# AET_mcu.net
KiCad netlist of a schematic drawn in Altium Designer
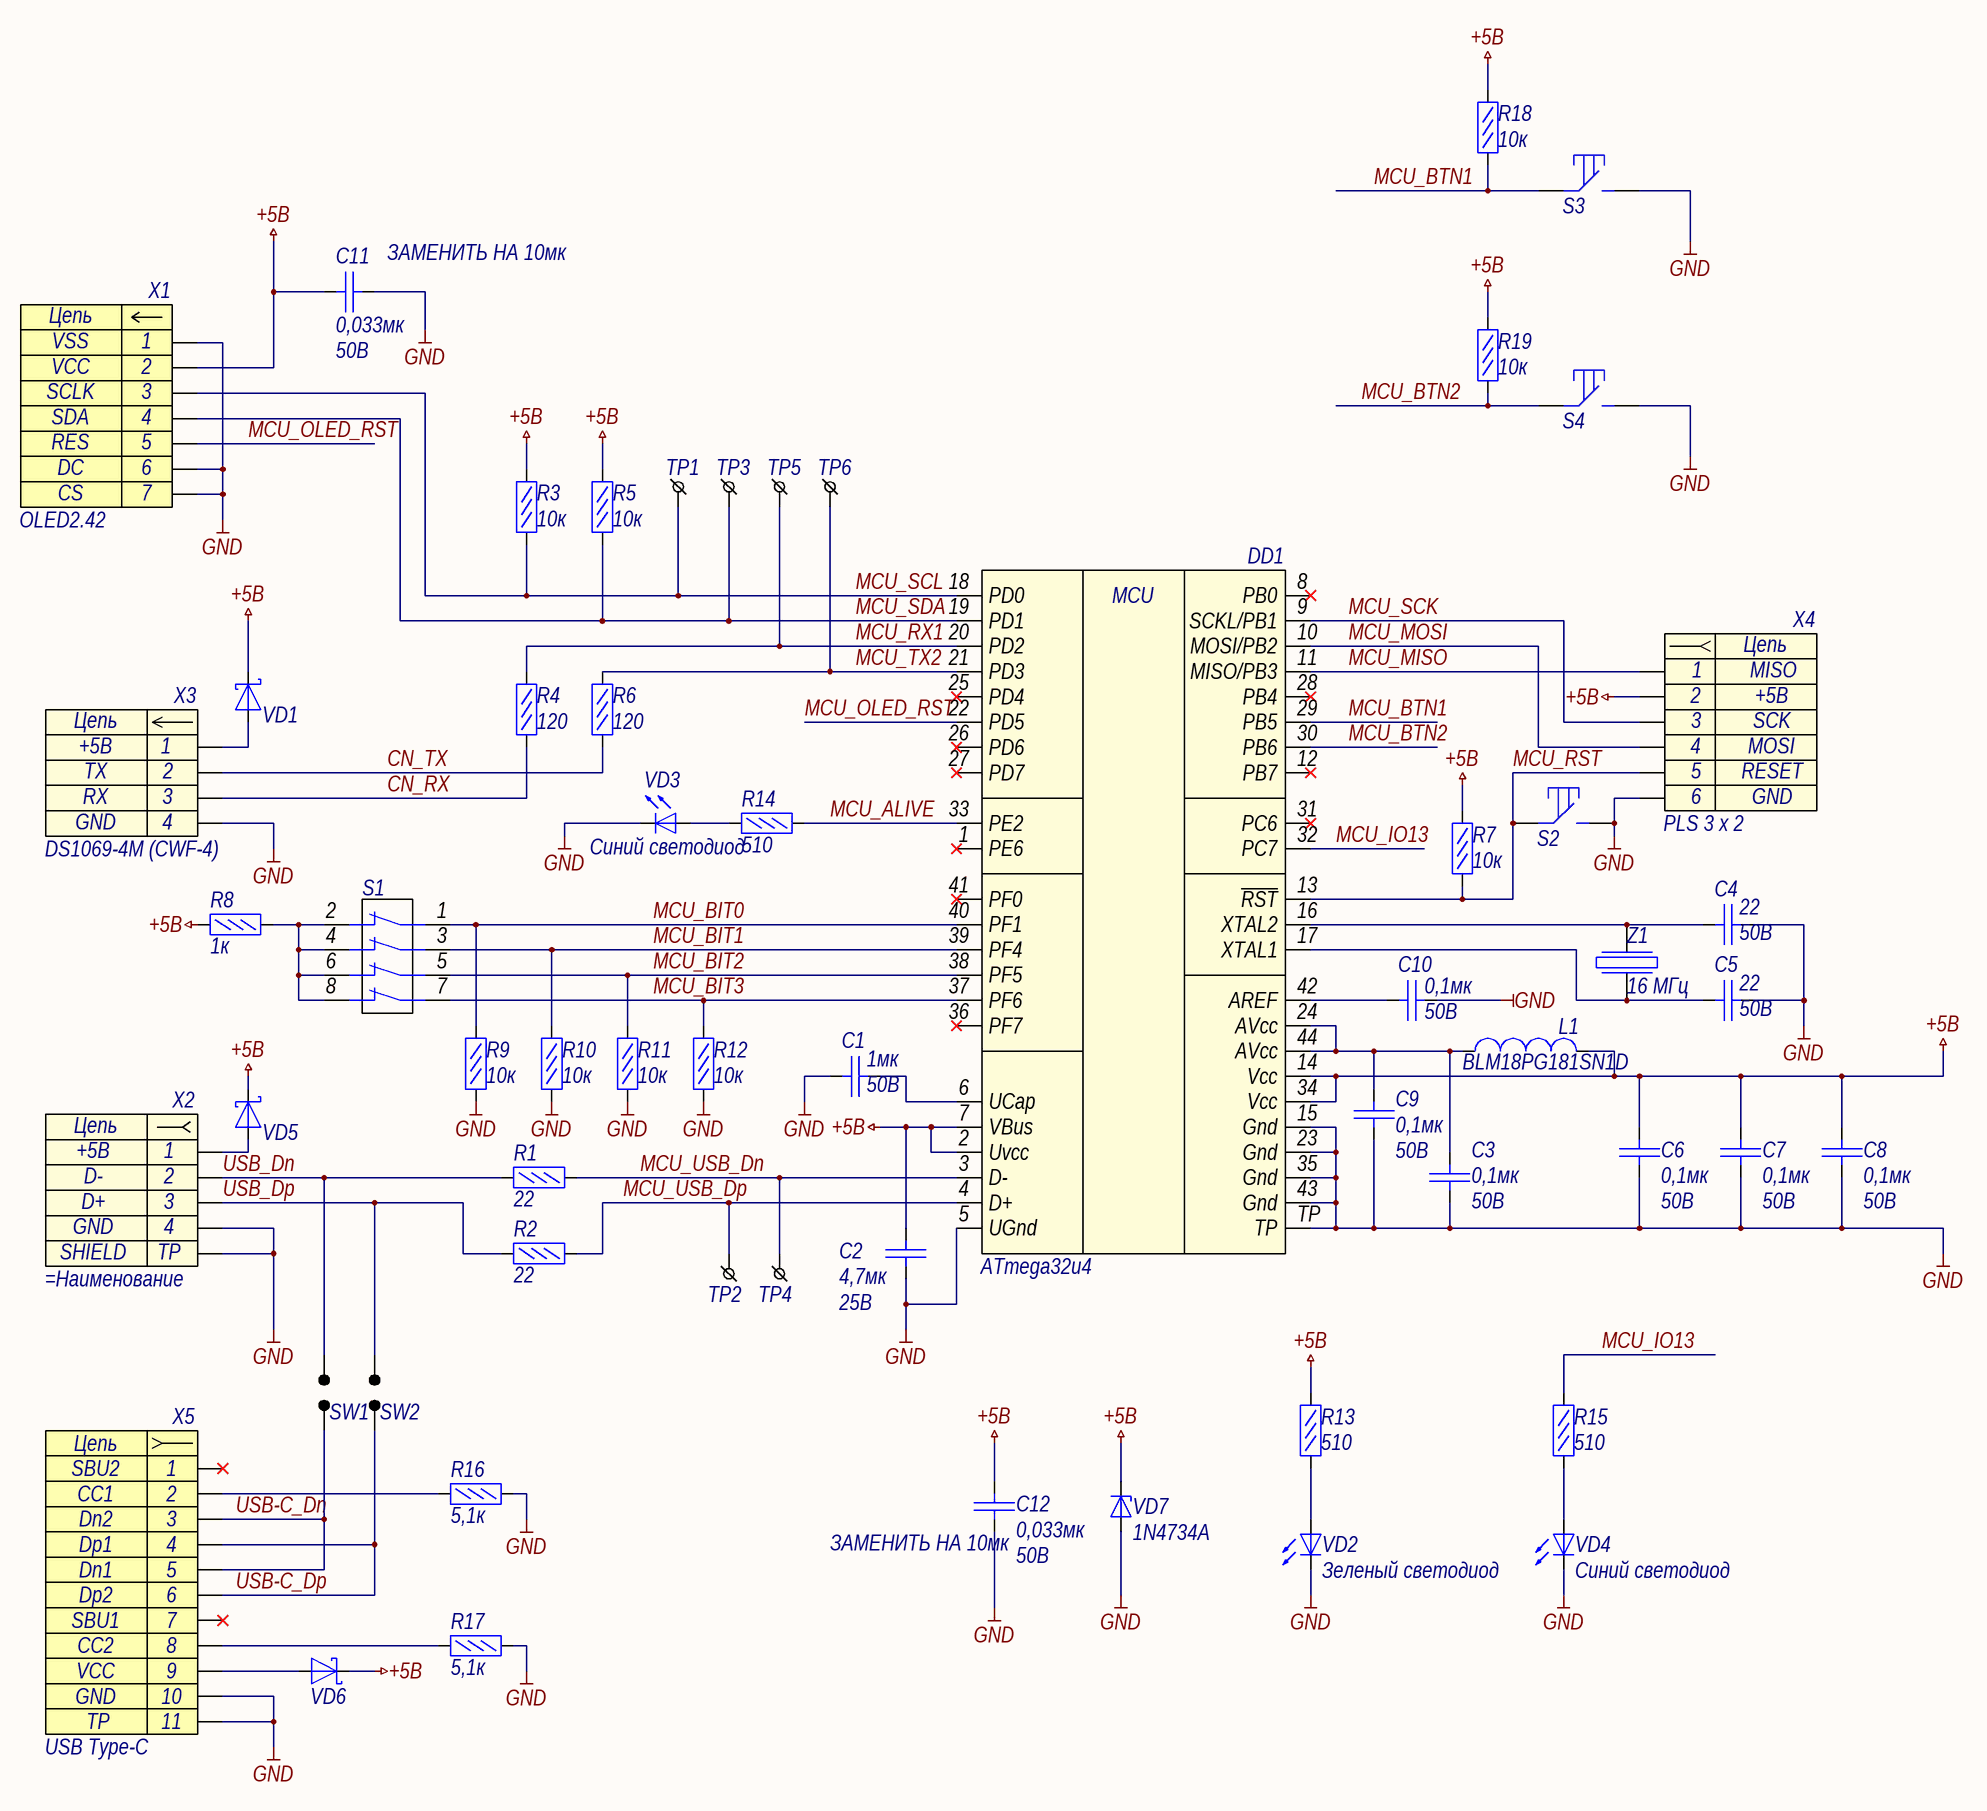
[diagram p0: AET_mcu.SchDoc]

(export (version "E")
  (design (tool "Eeschema 10.0.6"))
  (components
    (comp (ref "C1")
      (value "1мк")
      (footprint "C0603")
      (description "Конденсатор кер. 1мкФ 50В")
      (fields (field (name "MANUFACTURER") "Yageo") (field (name "VOLTAGE") "50В"))
      (libsource (lib "capacitors") (part "CC0603KRX7R9BB105"))
    )
    (comp (ref "C2")
      (value "4,7мк")
      (footprint "C0603")
      (description "Конденсатор кер. 4,7мкФ 25В")
      (fields (field (name "MANUFACTURER") "Yageo") (field (name "VOLTAGE") "25В"))
      (libsource (lib "capacitors") (part "CC0603KRX5R8BB475"))
    )
    (comp (ref "C3")
      (value "0,1мк")
      (footprint "C0603")
      (description "Конденсатор кер. 0,1мкФ 50В")
      (fields (field (name "MANUFACTURER") "Yageo") (field (name "VOLTAGE") "50В"))
      (libsource (lib "capacitors") (part "CC0603JPX7R9BB104"))
    )
    (comp (ref "C4")
      (value "22")
      (footprint "C0603")
      (description "Конденсатор кер. 22пФ 50В")
      (fields (field (name "MANUFACTURER") "Yageo") (field (name "VOLTAGE") "50В"))
      (libsource (lib "capacitors") (part "CC0603JRNPO9BN220"))
    )
    (comp (ref "C5")
      (value "22")
      (footprint "C0603")
      (description "Конденсатор кер. 22пФ 50В")
      (fields (field (name "MANUFACTURER") "Yageo") (field (name "VOLTAGE") "50В"))
      (libsource (lib "capacitors") (part "CC0603JRNPO9BN220"))
    )
    (comp (ref "C6")
      (value "0,1мк")
      (footprint "C0603")
      (description "Конденсатор кер. 0,1мкФ 50В")
      (fields (field (name "MANUFACTURER") "Yageo") (field (name "VOLTAGE") "50В"))
      (libsource (lib "capacitors") (part "CC0603JPX7R9BB104"))
    )
    (comp (ref "C7")
      (value "0,1мк")
      (footprint "C0603")
      (description "Конденсатор кер. 0,1мкФ 50В")
      (fields (field (name "MANUFACTURER") "Yageo") (field (name "VOLTAGE") "50В"))
      (libsource (lib "capacitors") (part "CC0603JPX7R9BB104"))
    )
    (comp (ref "C8")
      (value "0,1мк")
      (footprint "C0603")
      (description "Конденсатор кер. 0,1мкФ 50В")
      (fields (field (name "MANUFACTURER") "Yageo") (field (name "VOLTAGE") "50В"))
      (libsource (lib "capacitors") (part "CC0603JPX7R9BB104"))
    )
    (comp (ref "C9")
      (value "0,1мк")
      (footprint "C0603")
      (description "Конденсатор кер. 0,1мкФ 50В")
      (fields (field (name "MANUFACTURER") "Yageo") (field (name "VOLTAGE") "50В"))
      (libsource (lib "capacitors") (part "CC0603JPX7R9BB104"))
    )
    (comp (ref "C10")
      (value "0,1мк")
      (footprint "C0603")
      (description "Конденсатор кер. 0,1мкФ 50В")
      (fields (field (name "MANUFACTURER") "Yageo") (field (name "VOLTAGE") "50В"))
      (libsource (lib "capacitors") (part "CC0603JPX7R9BB104"))
    )
    (comp (ref "C11")
      (value "0,033мк")
      (footprint "C1206")
      (description "Конденсатор кер. 0,033мкФ 50В NP0")
      (fields (field (name "MANUFACTURER") "Murata") (field (name "VOLTAGE") "50В"))
      (libsource (lib "capacitors") (part "GRM3195C1H333J"))
    )
    (comp (ref "C12")
      (value "0,033мк")
      (footprint "C1206")
      (description "Конденсатор кер. 0,033мкФ 50В NP0")
      (fields (field (name "MANUFACTURER") "Murata") (field (name "VOLTAGE") "50В"))
      (libsource (lib "capacitors") (part "GRM3195C1H333J"))
    )
    (comp (ref "DD1")
      (value "ATmega32u4")
      (footprint "UNIVERSAL_ATMEGA32U4")
      (description "Микроконтроллер AVR 8-bit")
      (libsource (lib "MCU") (part "ATMEGA32U4"))
    )
    (comp (ref "L1")
      (value "BLM18PG181SN1D")
      (footprint "L0603")
      (description "Ферритовая бусина 180Ом 1,5А")
      (fields (field (name "MANUFACTURER") "Murata"))
      (libsource (lib "inductance") (part "BLM18PG181SN1D"))
    )
    (comp (ref "R1")
      (value "22")
      (footprint "R0603")
      (description "Резистор 22 Ом 0,1Вт 1%")
      (fields (field (name "MANUFACTURER") "YAGEO") (field (name "TOLERANCE") "1%"))
      (libsource (lib "resistors") (part "RC0603FR-0722RL"))
    )
    (comp (ref "R2")
      (value "22")
      (footprint "R0603")
      (description "Резистор 22 Ом 0,1Вт 1%")
      (fields (field (name "MANUFACTURER") "YAGEO") (field (name "TOLERANCE") "1%"))
      (libsource (lib "resistors") (part "RC0603FR-0722RL"))
    )
    (comp (ref "R3")
      (value "10к")
      (footprint "R0603")
      (description "Резистор 10кОм 0,063Вт 1%")
      (fields (field (name "MANUFACTURER") "YAGEO") (field (name "TOLERANCE") "1%"))
      (libsource (lib "resistors") (part "RC0603FR-0710KL"))
    )
    (comp (ref "R4")
      (value "120")
      (footprint "R0603")
      (description "Резистор 120Ом 0,063Вт 1%")
      (fields (field (name "MANUFACTURER") "YAGEO") (field (name "TOLERANCE") "1%"))
      (libsource (lib "resistors") (part "RC0603FR-07120RL"))
    )
    (comp (ref "R5")
      (value "10к")
      (footprint "R0603")
      (description "Резистор 10кОм 0,063Вт 1%")
      (fields (field (name "MANUFACTURER") "YAGEO") (field (name "TOLERANCE") "1%"))
      (libsource (lib "resistors") (part "RC0603FR-0710KL"))
    )
    (comp (ref "R6")
      (value "120")
      (footprint "R0603")
      (description "Резистор 120Ом 0,063Вт 1%")
      (fields (field (name "MANUFACTURER") "YAGEO") (field (name "TOLERANCE") "1%"))
      (libsource (lib "resistors") (part "RC0603FR-07120RL"))
    )
    (comp (ref "R7")
      (value "10к")
      (footprint "R0603")
      (description "Резистор 10кОм 0,063Вт 1%")
      (fields (field (name "MANUFACTURER") "YAGEO") (field (name "TOLERANCE") "1%"))
      (libsource (lib "resistors") (part "RC0603FR-0710KL"))
    )
    (comp (ref "R8")
      (value "1к")
      (footprint "R0603")
      (description "Резистор 1кОм 0,063Вт 1%")
      (fields (field (name "MANUFACTURER") "YAGEO") (field (name "TOLERANCE") "1%"))
      (libsource (lib "resistors") (part "RC0603FR-071KL"))
    )
    (comp (ref "R9")
      (value "10к")
      (footprint "R0603")
      (description "Резистор 10кОм 0,063Вт 1%")
      (fields (field (name "MANUFACTURER") "YAGEO") (field (name "TOLERANCE") "1%"))
      (libsource (lib "resistors") (part "RC0603FR-0710KL"))
    )
    (comp (ref "R10")
      (value "10к")
      (footprint "R0603")
      (description "Резистор 10кОм 0,063Вт 1%")
      (fields (field (name "MANUFACTURER") "YAGEO") (field (name "TOLERANCE") "1%"))
      (libsource (lib "resistors") (part "RC0603FR-0710KL"))
    )
    (comp (ref "R11")
      (value "10к")
      (footprint "R0603")
      (description "Резистор 10кОм 0,063Вт 1%")
      (fields (field (name "MANUFACTURER") "YAGEO") (field (name "TOLERANCE") "1%"))
      (libsource (lib "resistors") (part "RC0603FR-0710KL"))
    )
    (comp (ref "R12")
      (value "10к")
      (footprint "R0603")
      (description "Резистор 10кОм 0,063Вт 1%")
      (fields (field (name "MANUFACTURER") "YAGEO") (field (name "TOLERANCE") "1%"))
      (libsource (lib "resistors") (part "RC0603FR-0710KL"))
    )
    (comp (ref "R13")
      (value "510")
      (footprint "R0603")
      (description "Резистор 510 Ом 0,1Вт 1%")
      (fields (field (name "MANUFACTURER") "YAGEO") (field (name "TOLERANCE") "1%"))
      (libsource (lib "") (part "RC0603FR-07510RL_1"))
    )
    (comp (ref "R14")
      (value "510")
      (footprint "R0603")
      (description "Резистор 510 Ом 0,1Вт 1%")
      (fields (field (name "MANUFACTURER") "YAGEO") (field (name "TOLERANCE") "1%"))
      (libsource (lib "") (part "RC0603FR-07510RL_2"))
    )
    (comp (ref "R15")
      (value "510")
      (footprint "R0603")
      (description "Резистор 510 Ом 0,1Вт 1%")
      (fields (field (name "MANUFACTURER") "YAGEO") (field (name "TOLERANCE") "1%"))
      (libsource (lib "resistors") (part "RC0603FR-07510RL"))
    )
    (comp (ref "R16")
      (value "5,1к")
      (footprint "R0603")
      (description "Резистор 5,1кОм 0,1Вт 1%")
      (fields (field (name "MANUFACTURER") "YAGEO") (field (name "TOLERANCE") "1%"))
      (libsource (lib "resistors") (part "RC0603FR-075K1L"))
    )
    (comp (ref "R17")
      (value "5,1к")
      (footprint "R0603")
      (description "Резистор 5,1кОм 0,1Вт 1%")
      (fields (field (name "MANUFACTURER") "YAGEO") (field (name "TOLERANCE") "1%"))
      (libsource (lib "resistors") (part "RC0603FR-075K1L"))
    )
    (comp (ref "R18")
      (value "10к")
      (footprint "R0603")
      (description "Резистор 10кОм 0,063Вт 1%")
      (fields (field (name "MANUFACTURER") "YAGEO") (field (name "TOLERANCE") "1%"))
      (libsource (lib "") (part "RC0603FR-0710KL_1"))
    )
    (comp (ref "R19")
      (value "10к")
      (footprint "R0603")
      (description "Резистор 10кОм 0,063Вт 1%")
      (fields (field (name "MANUFACTURER") "YAGEO") (field (name "TOLERANCE") "1%"))
      (libsource (lib "") (part "RC0603FR-0710KL_1"))
    )
    (comp (ref "S1") (value "~") (footprint "A6S-4102-H") (libsource (lib "switches") (part "A6S-4102-H")))
    (comp (ref "S2")
      (value "IT-1187")
      (footprint "it-1187")
      (description "тактовая кнопка SMD")
      (libsource (lib "switches") (part "IT-1187"))
    )
    (comp (ref "S3")
      (value "IT-1198E")
      (footprint "IT-1198E")
      (description "боковая тактовая кнопка SMD")
      (libsource (lib "switches") (part "IT-1198E"))
    )
    (comp (ref "S4")
      (value "IT-1198E")
      (footprint "IT-1198E")
      (description "боковая тактовая кнопка SMD")
      (libsource (lib "switches") (part "IT-1198E"))
    )
    (comp (ref "SW1")
      (value "~")
      (footprint "JUMPER_SOLDERED_3x1")
      (description "Запаиваемая перемычка")
      (libsource (lib "mount_parts") (part "jumper"))
    )
    (comp (ref "SW2")
      (value "~")
      (footprint "JUMPER_SOLDERED_3x1")
      (description "Запаиваемая перемычка")
      (libsource (lib "mount_parts") (part "jumper"))
    )
    (comp (ref "TP1")
      (value "SCL")
      (footprint "TP_0,6X1")
      (libsource (lib "mount_parts") (part "TESTPOINT_HOLE"))
    )
    (comp (ref "TP2")
      (value "USB_Dp")
      (footprint "TP_0,6X1")
      (libsource (lib "mount_parts") (part "TESTPOINT_HOLE"))
    )
    (comp (ref "TP3")
      (value "SDA")
      (footprint "TP_0,6X1")
      (libsource (lib "mount_parts") (part "TESTPOINT_HOLE"))
    )
    (comp (ref "TP4")
      (value "USB_Dn")
      (footprint "TP_0,6X1")
      (libsource (lib "mount_parts") (part "TESTPOINT_HOLE"))
    )
    (comp (ref "TP5")
      (value "RX")
      (footprint "TP_0,6X1")
      (libsource (lib "mount_parts") (part "TESTPOINT_HOLE"))
    )
    (comp (ref "TP6")
      (value "TX")
      (footprint "TP_0,6X1")
      (libsource (lib "mount_parts") (part "TESTPOINT_HOLE"))
    )
    (comp (ref "VD1")
      (value "1N5817WS")
      (footprint "SOD323")
      (description "Диод Шоттки 1N5817WS 20V 1А 0.45V")
      (fields (field (name "VOLTAGE") "20В"))
      (libsource (lib "diodes") (part "1N5817WS"))
    )
    (comp (ref "VD2")
      (value "Зеленый светодиод")
      (footprint "VD0603")
      (description "Светодтод зеленый SMD Foryard Optoelectronics Co.")
      (libsource (lib "diodes") (part "FYLS-0603BUGC"))
    )
    (comp (ref "VD3")
      (value "Синий светодиод")
      (footprint "VD0603")
      (description "Светодтод синий SMD Foryard Optoelectronics Co.")
      (libsource (lib "diodes") (part "FYLS-0603BUBC"))
    )
    (comp (ref "VD4")
      (value "Синий светодиод")
      (footprint "VD0603")
      (description "Светодтод синий SMD Foryard Optoelectronics Co.")
      (libsource (lib "diodes") (part "FYLS-0603BUBC"))
    )
    (comp (ref "VD5")
      (value "1N5817WS")
      (footprint "SOD323")
      (description "Диод Шоттки 1N5817WS 20V 1А 0.45V")
      (fields (field (name "VOLTAGE") "20В"))
      (libsource (lib "diodes") (part "1N5817WS"))
    )
    (comp (ref "VD6")
      (value "1N5817WS")
      (footprint "SOD323")
      (description "Диод Шоттки 1N5817WS 20V 1А 0.45V")
      (fields (field (name "VOLTAGE") "20В"))
      (libsource (lib "diodes") (part "1N5817WS"))
    )
    (comp (ref "VD7")
      (value "1N4734A")
      (footprint "DO-41 Vertical")
      (description "Стабилитрон 5.6В, 5%, 1Вт, 1N4734A")
      (libsource (lib "diodes") (part "1N4734A"))
    )
    (comp (ref "X1")
      (value "OLED2.42")
      (footprint "OLED2.42-PLS2.54-1x7")
      (description "OLED дисплей 2.42inc - PLS2.54 - 1x7")
      (libsource (lib "headers") (part "OLED2,42 - header"))
    )
    (comp (ref "X2") (value "~") (footprint "USB-A") (libsource (lib "headers") (part "HEADER-USB-2.0")))
    (comp (ref "X3")
      (value "DS1069-4M (CWF-4)")
      (footprint "CWF-4")
      (description "Разъем - 4 конт. прямая вилка на плату")
      (fields (field (name "NAME") "DS1069-4M (CWF-4)"))
      (libsource (lib "headers") (part "CWF-4"))
    )
    (comp (ref "X4")
      (value "PLS 3 x 2")
      (footprint "pls-2,54-3x2-tht-v")
      (description "Разъем - 6 конт. 2x3, шаг 2,54 мм")
      (libsource (lib "headers") (part "PLS-3x2 ICSP"))
    )
    (comp (ref "X5")
      (value "USB Type-C")
      (footprint "USB4105-15-A-120")
      (description "USB Type-C USB4105-GF-A / GCT")
      (libsource (lib "headers") (part "USB4105-15-A-120"))
    )
    (comp (ref "Z1")
      (value "16 MГц")
      (footprint "QSMD3.2x2.5")
      (description "Кварцевый резонатор 16МГц")
      (fields (field (name "PARTNUMBER") "12.88605"))
      (libsource (lib "oscillators") (part "KX-7-16.0MHz"))
    )
  )
  (nets
    (net (code "1") (name "+5В") (class "Default")
      (node (ref "C11") (pin "2") (pinfunction "2_2") (pintype "passive"))
      (node (ref "C12") (pin "1") (pinfunction "1_1") (pintype "passive"))
      (node (ref "C2") (pin "2") (pinfunction "2_2") (pintype "passive"))
      (node (ref "C6") (pin "2") (pinfunction "2_2") (pintype "passive"))
      (node (ref "C7") (pin "2") (pinfunction "2_2") (pintype "passive"))
      (node (ref "C8") (pin "2") (pinfunction "2_2") (pintype "passive"))
      (node (ref "DD1") (pin "14") (pinfunction "Vcc_14") (pintype "passive"))
      (node (ref "DD1") (pin "2") (pinfunction "Uvcc_2") (pintype "passive"))
      (node (ref "DD1") (pin "34") (pinfunction "Vcc_34") (pintype "passive"))
      (node (ref "DD1") (pin "7") (pinfunction "VBus_7") (pintype "passive"))
      (node (ref "L1") (pin "2") (pinfunction "4_2") (pintype "passive"))
      (node (ref "R13") (pin "2") (pinfunction "2_2") (pintype "passive"))
      (node (ref "R18") (pin "1") (pinfunction "1_1") (pintype "passive"))
      (node (ref "R19") (pin "1") (pinfunction "1_1") (pintype "passive"))
      (node (ref "R3") (pin "2") (pinfunction "2_2") (pintype "passive"))
      (node (ref "R5") (pin "2") (pinfunction "2_2") (pintype "passive"))
      (node (ref "R7") (pin "2") (pinfunction "2_2") (pintype "passive"))
      (node (ref "R8") (pin "2") (pinfunction "2_2") (pintype "passive"))
      (node (ref "VD1") (pin "1") (pinfunction "K_1") (pintype "passive"))
      (node (ref "VD5") (pin "1") (pinfunction "K_1") (pintype "passive"))
      (node (ref "VD6") (pin "1") (pinfunction "K_1") (pintype "passive"))
      (node (ref "VD7") (pin "2") (pinfunction "K_2") (pintype "passive"))
      (node (ref "X1") (pin "2") (pinfunction "2_2") (pintype "passive"))
      (node (ref "X4") (pin "2") (pinfunction "2_2") (pintype "passive"))
    )
    (net (code "2") (name "/CN_RX") (class "Default")
      (node (ref "R4") (pin "1") (pinfunction "1_1") (pintype "passive"))
      (node (ref "X3") (pin "3") (pinfunction "3_3") (pintype "passive"))
    )
    (net (code "3") (name "/CN_TX") (class "Default")
      (node (ref "R6") (pin "1") (pinfunction "1_1") (pintype "passive"))
      (node (ref "X3") (pin "2") (pinfunction "2_2") (pintype "passive"))
    )
    (net (code "4") (name "/MCU_ALIVE") (class "Default")
      (node (ref "DD1") (pin "33") (pinfunction "PE2_33") (pintype "passive"))
      (node (ref "R14") (pin "1") (pinfunction "1_1") (pintype "passive"))
    )
    (net (code "5") (name "/MCU_BIT0") (class "Default")
      (node (ref "DD1") (pin "40") (pinfunction "PF1_40") (pintype "passive"))
      (node (ref "R9") (pin "2") (pinfunction "2_2") (pintype "passive"))
      (node (ref "S1") (pin "1") (pinfunction "1_1") (pintype "passive"))
    )
    (net (code "6") (name "/MCU_BIT1") (class "Default")
      (node (ref "DD1") (pin "39") (pinfunction "PF4_39") (pintype "passive"))
      (node (ref "R10") (pin "2") (pinfunction "2_2") (pintype "passive"))
      (node (ref "S1") (pin "3") (pinfunction "3_3") (pintype "passive"))
    )
    (net (code "7") (name "/MCU_BIT2") (class "Default")
      (node (ref "DD1") (pin "38") (pinfunction "PF5_38") (pintype "passive"))
      (node (ref "R11") (pin "2") (pinfunction "2_2") (pintype "passive"))
      (node (ref "S1") (pin "5") (pinfunction "5_5") (pintype "passive"))
    )
    (net (code "8") (name "/MCU_BIT3") (class "Default")
      (node (ref "DD1") (pin "37") (pinfunction "PF6_37") (pintype "passive"))
      (node (ref "R12") (pin "2") (pinfunction "2_2") (pintype "passive"))
      (node (ref "S1") (pin "7") (pinfunction "7_7") (pintype "passive"))
    )
    (net (code "9") (name "/MCU_BTN1") (class "Default")
      (node (ref "DD1") (pin "29") (pinfunction "PB5_29") (pintype "passive"))
      (node (ref "R18") (pin "2") (pinfunction "2_2") (pintype "passive"))
      (node (ref "S3") (pin "1") (pinfunction "1_1") (pintype "passive"))
    )
    (net (code "10") (name "/MCU_BTN2") (class "Default")
      (node (ref "DD1") (pin "30") (pinfunction "PB6_30") (pintype "passive"))
      (node (ref "R19") (pin "2") (pinfunction "2_2") (pintype "passive"))
      (node (ref "S4") (pin "1") (pinfunction "1_1") (pintype "passive"))
    )
    (net (code "11") (name "/MCU_IO13") (class "Default")
      (node (ref "DD1") (pin "32") (pinfunction "PC7_32") (pintype "passive"))
      (node (ref "R15") (pin "1") (pinfunction "1_1") (pintype "passive"))
    )
    (net (code "12") (name "/MCU_MISO") (class "Default")
      (node (ref "DD1") (pin "11") (pinfunction "MISO/PB3_11") (pintype "passive"))
      (node (ref "X4") (pin "1") (pinfunction "1_1") (pintype "passive"))
    )
    (net (code "13") (name "/MCU_MOSI") (class "Default")
      (node (ref "DD1") (pin "10") (pinfunction "MOSI/PB2_10") (pintype "passive"))
      (node (ref "X4") (pin "4") (pinfunction "4_4") (pintype "passive"))
    )
    (net (code "14") (name "/MCU_OLED_RST") (class "Default")
      (node (ref "DD1") (pin "22") (pinfunction "PD5_22") (pintype "passive"))
      (node (ref "X1") (pin "5") (pinfunction "5_5") (pintype "passive"))
    )
    (net (code "15") (name "/MCU_RST") (class "Default")
      (node (ref "DD1") (pin "13") (pinfunction "~{RST}_13") (pintype "passive"))
      (node (ref "R7") (pin "1") (pinfunction "1_1") (pintype "passive"))
      (node (ref "S2") (pin "1") (pinfunction "1_1") (pintype "passive"))
      (node (ref "X4") (pin "5") (pinfunction "5_5") (pintype "passive"))
    )
    (net (code "16") (name "/MCU_RX1") (class "Default")
      (node (ref "DD1") (pin "20") (pinfunction "PD2_20") (pintype "passive"))
      (node (ref "R4") (pin "2") (pinfunction "2_2") (pintype "passive"))
      (node (ref "TP5") (pin "1") (pinfunction "1_1") (pintype "passive"))
    )
    (net (code "17") (name "/MCU_SCK") (class "Default")
      (node (ref "DD1") (pin "9") (pinfunction "SCKL/PB1_9") (pintype "passive"))
      (node (ref "X4") (pin "3") (pinfunction "3_3") (pintype "passive"))
    )
    (net (code "18") (name "/MCU_SCL") (class "Default")
      (node (ref "DD1") (pin "18") (pinfunction "PD0_18") (pintype "passive"))
      (node (ref "R3") (pin "1") (pinfunction "1_1") (pintype "passive"))
      (node (ref "TP1") (pin "1") (pinfunction "1_1") (pintype "passive"))
      (node (ref "X1") (pin "3") (pinfunction "3_3") (pintype "passive"))
    )
    (net (code "19") (name "/MCU_SDA") (class "Default")
      (node (ref "DD1") (pin "19") (pinfunction "PD1_19") (pintype "passive"))
      (node (ref "R5") (pin "1") (pinfunction "1_1") (pintype "passive"))
      (node (ref "TP3") (pin "1") (pinfunction "1_1") (pintype "passive"))
      (node (ref "X1") (pin "4") (pinfunction "4_4") (pintype "passive"))
    )
    (net (code "20") (name "/MCU_TX2") (class "Default")
      (node (ref "DD1") (pin "21") (pinfunction "PD3_21") (pintype "passive"))
      (node (ref "R6") (pin "2") (pinfunction "2_2") (pintype "passive"))
      (node (ref "TP6") (pin "1") (pinfunction "1_1") (pintype "passive"))
    )
    (net (code "21") (name "/MCU_USB_Dn") (class "Default")
      (node (ref "DD1") (pin "3") (pinfunction "D-_3") (pintype "passive"))
      (node (ref "R1") (pin "2") (pinfunction "2_2") (pintype "passive"))
      (node (ref "TP4") (pin "1") (pinfunction "1_1") (pintype "passive"))
    )
    (net (code "22") (name "/MCU_USB_Dp") (class "Default")
      (node (ref "DD1") (pin "4") (pinfunction "D+_4") (pintype "passive"))
      (node (ref "R2") (pin "2") (pinfunction "2_2") (pintype "passive"))
      (node (ref "TP2") (pin "1") (pinfunction "1_1") (pintype "passive"))
    )
    (net (code "23") (name "/USB-C_Dn") (class "Default")
      (node (ref "SW1") (pin "1") (pinfunction "1_1") (pintype "passive"))
      (node (ref "X5") (pin "3") (pinfunction "B7_3") (pintype "passive"))
      (node (ref "X5") (pin "5") (pinfunction "A7_5") (pintype "passive"))
    )
    (net (code "24") (name "/USB-C_Dp") (class "Default")
      (node (ref "SW2") (pin "1") (pinfunction "1_1") (pintype "passive"))
      (node (ref "X5") (pin "4") (pinfunction "A6_4") (pintype "passive"))
      (node (ref "X5") (pin "6") (pinfunction "B6_6") (pintype "passive"))
    )
    (net (code "25") (name "/USB_Dn") (class "Default")
      (node (ref "R1") (pin "1") (pinfunction "1_1") (pintype "passive"))
      (node (ref "SW1") (pin "2") (pinfunction "2_2") (pintype "passive"))
      (node (ref "X2") (pin "2") (pinfunction "2_2") (pintype "passive"))
    )
    (net (code "26") (name "/USB_Dp") (class "Default")
      (node (ref "R2") (pin "1") (pinfunction "1_1") (pintype "passive"))
      (node (ref "SW2") (pin "2") (pinfunction "2_2") (pintype "passive"))
      (node (ref "X2") (pin "3") (pinfunction "3_3") (pintype "passive"))
    )
    (net (code "27") (name "GND") (class "Default")
      (node (ref "C1") (pin "1") (pinfunction "1_1") (pintype "passive"))
      (node (ref "C10") (pin "1") (pinfunction "1_1") (pintype "passive"))
      (node (ref "C11") (pin "1") (pinfunction "1_1") (pintype "passive"))
      (node (ref "C12") (pin "2") (pinfunction "2_2") (pintype "passive"))
      (node (ref "C2") (pin "1") (pinfunction "1_1") (pintype "passive"))
      (node (ref "C3") (pin "1") (pinfunction "1_1") (pintype "passive"))
      (node (ref "C4") (pin "2") (pinfunction "2_2") (pintype "passive"))
      (node (ref "C5") (pin "2") (pinfunction "2_2") (pintype "passive"))
      (node (ref "C6") (pin "1") (pinfunction "1_1") (pintype "passive"))
      (node (ref "C7") (pin "1") (pinfunction "1_1") (pintype "passive"))
      (node (ref "C8") (pin "1") (pinfunction "1_1") (pintype "passive"))
      (node (ref "C9") (pin "1") (pinfunction "1_1") (pintype "passive"))
      (node (ref "DD1") (pin "15") (pinfunction "Gnd_15") (pintype "passive"))
      (node (ref "DD1") (pin "23") (pinfunction "Gnd_23") (pintype "passive"))
      (node (ref "DD1") (pin "35") (pinfunction "Gnd_35") (pintype "passive"))
      (node (ref "DD1") (pin "43") (pinfunction "Gnd_43") (pintype "passive"))
      (node (ref "DD1") (pin "5") (pinfunction "UGnd_5") (pintype "passive"))
      (node (ref "DD1") (pin "TP") (pinfunction "TP_TP") (pintype "passive"))
      (node (ref "R10") (pin "1") (pinfunction "1_1") (pintype "passive"))
      (node (ref "R11") (pin "1") (pinfunction "1_1") (pintype "passive"))
      (node (ref "R12") (pin "1") (pinfunction "1_1") (pintype "passive"))
      (node (ref "R16") (pin "2") (pinfunction "2_2") (pintype "passive"))
      (node (ref "R17") (pin "2") (pinfunction "2_2") (pintype "passive"))
      (node (ref "R9") (pin "1") (pinfunction "1_1") (pintype "passive"))
      (node (ref "S2") (pin "2") (pinfunction "2_2") (pintype "passive"))
      (node (ref "S3") (pin "2") (pinfunction "2_2") (pintype "passive"))
      (node (ref "S4") (pin "2") (pinfunction "2_2") (pintype "passive"))
      (node (ref "VD2") (pin "2") (pinfunction "K_2") (pintype "passive"))
      (node (ref "VD3") (pin "2") (pinfunction "K_2") (pintype "passive"))
      (node (ref "VD4") (pin "2") (pinfunction "K_2") (pintype "passive"))
      (node (ref "VD7") (pin "1") (pinfunction "A_1") (pintype "passive"))
      (node (ref "X1") (pin "1") (pinfunction "1_1") (pintype "passive"))
      (node (ref "X1") (pin "6") (pinfunction "6_6") (pintype "passive"))
      (node (ref "X1") (pin "7") (pinfunction "7_7") (pintype "passive"))
      (node (ref "X2") (pin "4") (pinfunction "4_4") (pintype "passive"))
      (node (ref "X2") (pin "TP") (pinfunction "TP_TP") (pintype "passive"))
      (node (ref "X3") (pin "4") (pinfunction "4_4") (pintype "passive"))
      (node (ref "X4") (pin "6") (pinfunction "6_6") (pintype "passive"))
      (node (ref "X5") (pin "10") (pinfunction "VCC_10") (pintype "passive"))
      (node (ref "X5") (pin "TP") (pinfunction "TP_TP") (pintype "passive"))
    )
    (net (code "28") (name "Net-(DD1-AREF)") (class "Default")
      (node (ref "C10") (pin "2") (pinfunction "2_2") (pintype "passive"))
      (node (ref "DD1") (pin "42") (pinfunction "AREF_42") (pintype "passive"))
    )
    (net (code "29") (name "Net-(DD1-UCap)") (class "Default")
      (node (ref "C1") (pin "2") (pinfunction "2_2") (pintype "passive"))
      (node (ref "DD1") (pin "6") (pinfunction "UCap_6") (pintype "passive"))
    )
    (net (code "30") (name "Net-(DD1-XTAL1)") (class "Default")
      (node (ref "C5") (pin "1") (pinfunction "1_1") (pintype "passive"))
      (node (ref "DD1") (pin "17") (pinfunction "XTAL1_17") (pintype "passive"))
      (node (ref "Z1") (pin "1") (pintype "passive"))
    )
    (net (code "31") (name "Net-(DD1-XTAL2)") (class "Default")
      (node (ref "C4") (pin "1") (pinfunction "1_1") (pintype "passive"))
      (node (ref "DD1") (pin "16") (pinfunction "XTAL2_16") (pintype "passive"))
      (node (ref "Z1") (pin "2") (pintype "passive"))
    )
    (net (code "32") (name "Net-(L1-3)") (class "Default")
      (node (ref "C3") (pin "2") (pinfunction "2_2") (pintype "passive"))
      (node (ref "C9") (pin "2") (pinfunction "2_2") (pintype "passive"))
      (node (ref "DD1") (pin "24") (pinfunction "AVcc_24") (pintype "passive"))
      (node (ref "DD1") (pin "44") (pinfunction "AVcc_44") (pintype "passive"))
      (node (ref "L1") (pin "1") (pinfunction "3_1") (pintype "passive"))
    )
    (net (code "33") (name "Net-(R8-Pad1)") (class "Default")
      (node (ref "R8") (pin "1") (pinfunction "1_1") (pintype "passive"))
      (node (ref "S1") (pin "2") (pinfunction "2_2") (pintype "passive"))
      (node (ref "S1") (pin "4") (pinfunction "4_4") (pintype "passive"))
      (node (ref "S1") (pin "6") (pinfunction "6_6") (pintype "passive"))
      (node (ref "S1") (pin "8") (pinfunction "8_8") (pintype "passive"))
    )
    (net (code "34") (name "Net-(VD1-A)") (class "Default")
      (node (ref "VD1") (pin "2") (pinfunction "A_2") (pintype "passive"))
      (node (ref "X3") (pin "1") (pinfunction "1_1") (pintype "passive"))
    )
    (net (code "35") (name "Net-(VD2-A)") (class "Default")
      (node (ref "R13") (pin "1") (pinfunction "1_1") (pintype "passive"))
      (node (ref "VD2") (pin "1") (pinfunction "A_1") (pintype "passive"))
    )
    (net (code "36") (name "Net-(VD3-A)") (class "Default")
      (node (ref "R14") (pin "2") (pinfunction "2_2") (pintype "passive"))
      (node (ref "VD3") (pin "1") (pinfunction "A_1") (pintype "passive"))
    )
    (net (code "37") (name "Net-(VD4-A)") (class "Default")
      (node (ref "R15") (pin "2") (pinfunction "2_2") (pintype "passive"))
      (node (ref "VD4") (pin "1") (pinfunction "A_1") (pintype "passive"))
    )
    (net (code "38") (name "Net-(VD5-A)") (class "Default")
      (node (ref "VD5") (pin "2") (pinfunction "A_2") (pintype "passive"))
      (node (ref "X2") (pin "1") (pinfunction "1_1") (pintype "passive"))
    )
    (net (code "39") (name "Net-(VD6-A)") (class "Default")
      (node (ref "VD6") (pin "2") (pinfunction "A_2") (pintype "passive"))
      (node (ref "X5") (pin "9") (pinfunction "GND_9") (pintype "passive"))
    )
    (net (code "40") (name "Net-(X5-A5)") (class "Default")
      (node (ref "R16") (pin "1") (pinfunction "1_1") (pintype "passive"))
      (node (ref "X5") (pin "2") (pinfunction "A5_2") (pintype "passive"))
    )
    (net (code "41") (name "Net-(X5-B5)") (class "Default")
      (node (ref "R17") (pin "1") (pinfunction "1_1") (pintype "passive"))
      (node (ref "X5") (pin "8") (pinfunction "B5_8") (pintype "passive"))
    )
    (net (code "42") (name "unconnected-(DD1-PB0-Pad8)") (class "Default")
      (node (ref "DD1") (pin "8") (pinfunction "PB0_8") (pintype "passive+no_connect"))
    )
    (net (code "43") (name "unconnected-(DD1-PB4-Pad28)") (class "Default")
      (node (ref "DD1") (pin "28") (pinfunction "PB4_28") (pintype "passive+no_connect"))
    )
    (net (code "44") (name "unconnected-(DD1-PB7-Pad12)") (class "Default")
      (node (ref "DD1") (pin "12") (pinfunction "PB7_12") (pintype "passive+no_connect"))
    )
    (net (code "45") (name "unconnected-(DD1-PC6-Pad31)") (class "Default")
      (node (ref "DD1") (pin "31") (pinfunction "PC6_31") (pintype "passive+no_connect"))
    )
    (net (code "46") (name "unconnected-(DD1-PD4-Pad25)") (class "Default")
      (node (ref "DD1") (pin "25") (pinfunction "PD4_25") (pintype "passive+no_connect"))
    )
    (net (code "47") (name "unconnected-(DD1-PD6-Pad26)") (class "Default")
      (node (ref "DD1") (pin "26") (pinfunction "PD6_26") (pintype "passive+no_connect"))
    )
    (net (code "48") (name "unconnected-(DD1-PD7-Pad27)") (class "Default")
      (node (ref "DD1") (pin "27") (pinfunction "PD7_27") (pintype "passive+no_connect"))
    )
    (net (code "49") (name "unconnected-(DD1-PE6-Pad1)") (class "Default")
      (node (ref "DD1") (pin "1") (pinfunction "PE6_1") (pintype "passive+no_connect"))
    )
    (net (code "50") (name "unconnected-(DD1-PF0-Pad41)") (class "Default")
      (node (ref "DD1") (pin "41") (pinfunction "PF0_41") (pintype "passive+no_connect"))
    )
    (net (code "51") (name "unconnected-(DD1-PF7-Pad36)") (class "Default")
      (node (ref "DD1") (pin "36") (pinfunction "PF7_36") (pintype "passive+no_connect"))
    )
    (net (code "52") (name "unconnected-(X5-A8-Pad7)") (class "Default")
      (node (ref "X5") (pin "7") (pinfunction "A8_7") (pintype "passive+no_connect"))
    )
    (net (code "53") (name "unconnected-(X5-B8-Pad1)") (class "Default")
      (node (ref "X5") (pin "1") (pinfunction "B8_1") (pintype "passive+no_connect"))
    )
  )
)
